# revB.net
KiCad netlist of a schematic drawn in EAGLE
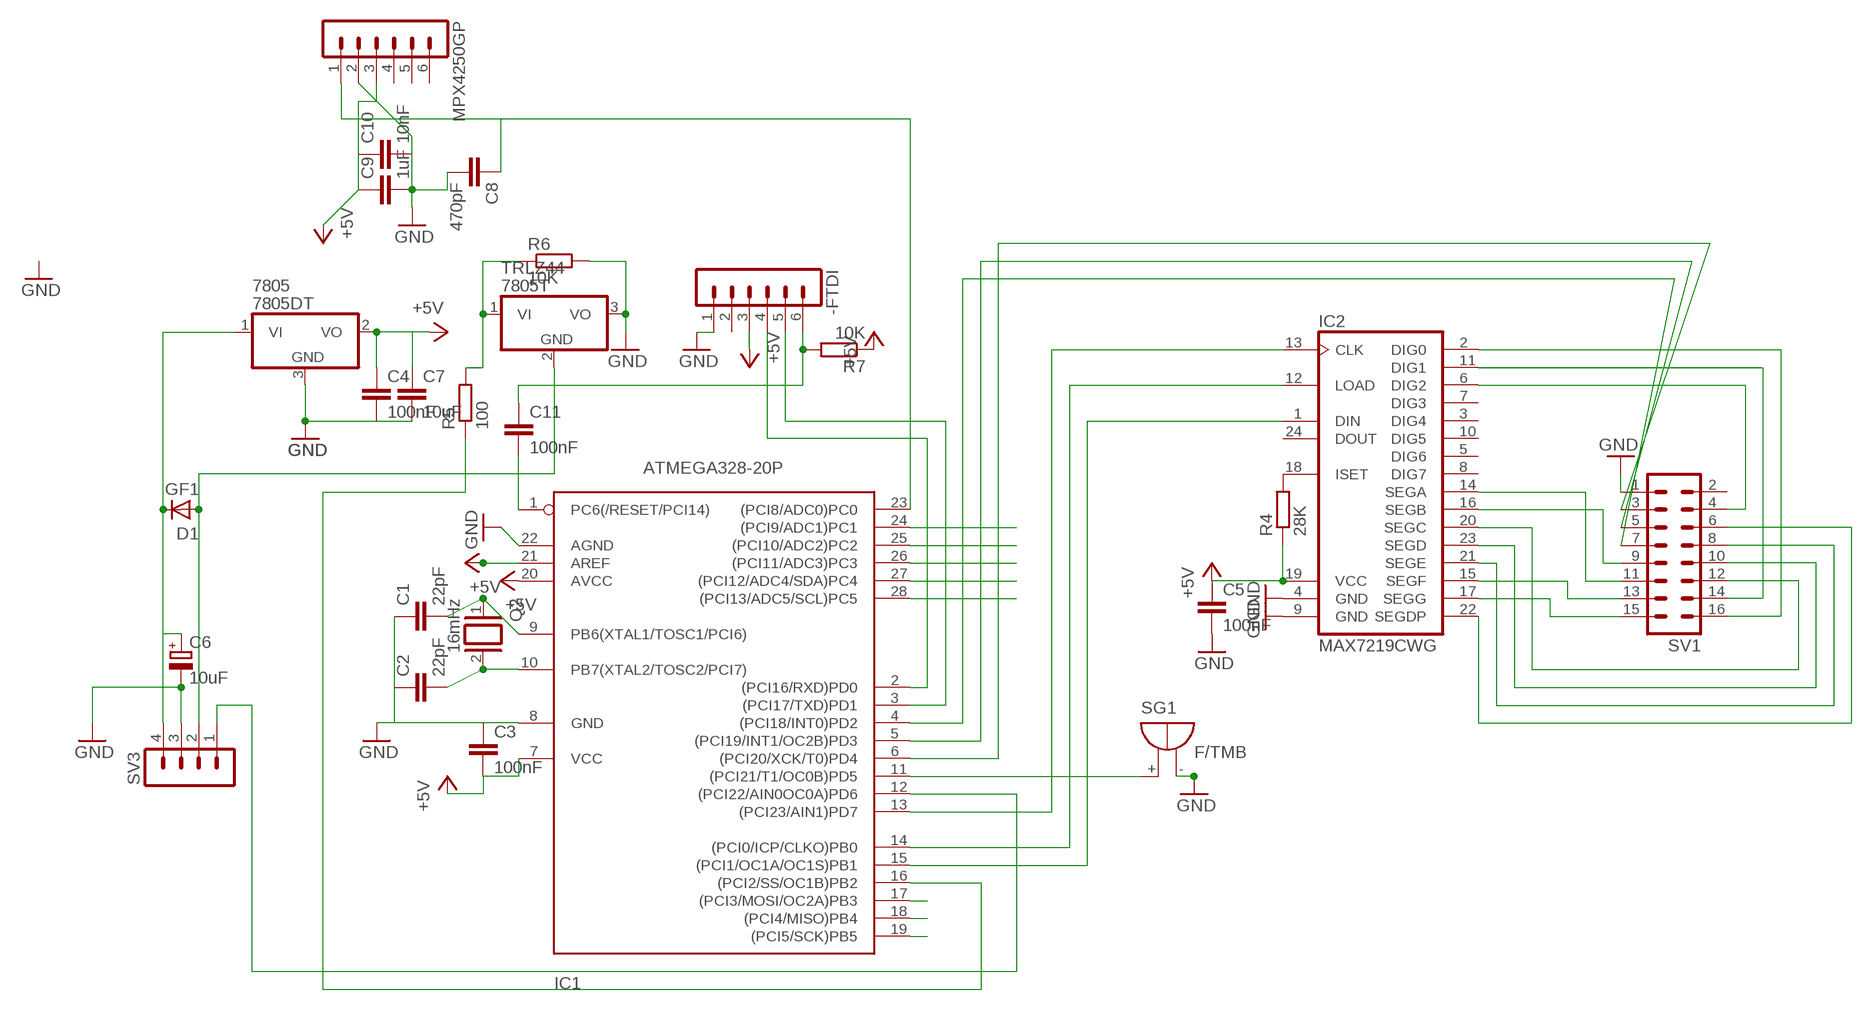
[diagram p0: schematic, sheet 1]

(export (version "E")
  (design (tool "Eeschema 10.0.6"))
  (components
    (comp (ref "-FTDI")
      (value "MA06-1")
      (footprint "eagle-import:MA06-1")
      (libsource (lib "eagle-import") (part "MA06-1"))
    )
    (comp (ref "7805")
      (value "7805DT")
      (footprint "eagle-import:TO252")
      (libsource (lib "eagle-import") (part "78DT05"))
    )
    (comp (ref "C1")
      (value "22pF")
      (footprint "eagle-import:C0805")
      (fields (field (name "MF") "MURATA") (field (name "MPN") "ERB21B5C2D220JDX1L"))
      (libsource (lib "eagle-import") (part "C-EUC0805"))
    )
    (comp (ref "C2")
      (value "22pF")
      (footprint "eagle-import:C0805")
      (fields (field (name "MF") "MURATA") (field (name "MPN") "ERB21B5C2D220JDX1L"))
      (libsource (lib "eagle-import") (part "C-EUC0805"))
    )
    (comp (ref "C3")
      (value "100nF")
      (footprint "eagle-import:C0805")
      (fields (field (name "MF") "KEMET") (field (name "MPN") "C0805X104K5RACTU"))
      (libsource (lib "eagle-import") (part "C-EUC0805"))
    )
    (comp (ref "C4")
      (value "100nF")
      (footprint "eagle-import:C0805")
      (fields (field (name "MF") "KEMET") (field (name "MPN") "C0805X104K5RACTU"))
      (libsource (lib "eagle-import") (part "C-EUC0805"))
    )
    (comp (ref "C5")
      (value "100nF")
      (footprint "eagle-import:C0805")
      (fields (field (name "MF") "KEMET") (field (name "MPN") "C0805X104K5RACTU"))
      (libsource (lib "eagle-import") (part "C-EUC0805"))
    )
    (comp (ref "C6")
      (value "10uF")
      (footprint "eagle-import:E2,5-6E")
      (libsource (lib "eagle-import") (part "CPOL-EUE2,5-6E"))
    )
    (comp (ref "C7")
      (value "10uF")
      (footprint "eagle-import:C0805")
      (fields (field (name "MF") "KEMET") (field (name "MPN") "C0805X104K5RACTU"))
      (libsource (lib "eagle-import") (part "C-EUC0805"))
    )
    (comp (ref "C8")
      (value "470pF")
      (footprint "eagle-import:C0805")
      (fields (field (name "MF") "KEMET") (field (name "MPN") "C0805X104K5RACTU"))
      (libsource (lib "eagle-import") (part "C-EUC0805"))
    )
    (comp (ref "C9")
      (value "1uF")
      (footprint "eagle-import:C0805")
      (fields (field (name "MF") "KEMET") (field (name "MPN") "C0805X104K5RACTU"))
      (libsource (lib "eagle-import") (part "C-EUC0805"))
    )
    (comp (ref "C10")
      (value "10nF")
      (footprint "eagle-import:C0805")
      (fields (field (name "MF") "KEMET") (field (name "MPN") "C0805X104K5RACTU"))
      (libsource (lib "eagle-import") (part "C-EUC0805"))
    )
    (comp (ref "C11")
      (value "100nF")
      (footprint "eagle-import:C0805")
      (fields (field (name "MF") "KEMET") (field (name "MPN") "C0805X104K5RACTU"))
      (libsource (lib "eagle-import") (part "C-EUC0805"))
    )
    (comp (ref "D1")
      (value "GF1")
      (footprint "eagle-import:SMA-DO214AC")
      (libsource (lib "eagle-import") (part "GF1"))
    )
    (comp (ref "IC1")
      (value "ATMEGA328-20P")
      (footprint "eagle-import:DIL28-3")
      (libsource (lib "eagle-import") (part "ATMEGA168P-20"))
    )
    (comp (ref "IC2")
      (value "MAX7219CWG")
      (footprint "eagle-import:MAX7219CWG")
      (libsource (lib "eagle-import") (part "MAX7219CWG"))
    )
    (comp (ref "MPX4250GP")
      (value "MA06-1")
      (footprint "eagle-import:MA06-1")
      (libsource (lib "eagle-import") (part "MA06-1"))
    )
    (comp (ref "Q2")
      (value "16mHz")
      (footprint "eagle-import:QS")
      (fields (field (name "MF") "EUROQUARTZ") (field (name "MPN") "16.000MHZ HC49/4H/30/50/40/18PF/ATF"))
      (libsource (lib "eagle-import") (part "XTAL/S"))
    )
    (comp (ref "R4")
      (value "28K")
      (footprint "eagle-import:R0805")
      (libsource (lib "eagle-import") (part "R-EU_R0805"))
    )
    (comp (ref "R5")
      (value "100")
      (footprint "eagle-import:R0805")
      (libsource (lib "eagle-import") (part "R-EU_R0805"))
    )
    (comp (ref "R6")
      (value "10K")
      (footprint "eagle-import:R0805")
      (libsource (lib "eagle-import") (part "R-EU_R0805"))
    )
    (comp (ref "R7")
      (value "10K")
      (footprint "eagle-import:R0805")
      (libsource (lib "eagle-import") (part "R-EU_R0805"))
    )
    (comp (ref "SG1")
      (value "F/TMB")
      (footprint "eagle-import:F_TMB")
      (libsource (lib "eagle-import") (part "F/TMB"))
    )
    (comp (ref "SV1")
      (value "MA08-2")
      (footprint "eagle-import:MA08-2")
      (libsource (lib "eagle-import") (part "MA08-2"))
    )
    (comp (ref "SV3")
      (value "MA04-1")
      (footprint "eagle-import:MA04-1")
      (libsource (lib "eagle-import") (part "MA04-1"))
    )
    (comp (ref "TRLZ44")
      (value "7805T")
      (footprint "eagle-import:TO220H")
      (libsource (lib "eagle-import") (part "78T05"))
    )
  )
  (nets
    (net (code "1") (name "+5V") (class "Default")
      (node (ref "-FTDI") (pin "3") (pinfunction "3_3") (pintype "passive"))
      (node (ref "7805") (pin "2") (pinfunction "VO_2") (pintype "passive"))
      (node (ref "C10") (pin "1") (pinfunction "1_1") (pintype "passive"))
      (node (ref "C3") (pin "2") (pinfunction "2_2") (pintype "passive"))
      (node (ref "C4") (pin "1") (pinfunction "1_1") (pintype "passive"))
      (node (ref "C5") (pin "1") (pinfunction "1_1") (pintype "passive"))
      (node (ref "C7") (pin "1") (pinfunction "1_1") (pintype "passive"))
      (node (ref "C9") (pin "1") (pinfunction "1_1") (pintype "passive"))
      (node (ref "IC1") (pin "20") (pinfunction "AVCC_20") (pintype "bidirectional"))
      (node (ref "IC1") (pin "21") (pinfunction "AREF_21") (pintype "bidirectional"))
      (node (ref "IC1") (pin "7") (pinfunction "VCC_7") (pintype "bidirectional"))
      (node (ref "IC2") (pin "19") (pinfunction "VCC_19") (pintype "power_in"))
      (node (ref "MPX4250GP") (pin "3") (pinfunction "3_3") (pintype "passive"))
      (node (ref "R4") (pin "1") (pinfunction "1_1") (pintype "passive"))
      (node (ref "R7") (pin "1") (pinfunction "1_1") (pintype "passive"))
    )
    (net (code "2") (name "GND") (class "Default")
      (node (ref "-FTDI") (pin "1") (pinfunction "1_1") (pintype "passive"))
      (node (ref "7805") (pin "3") (pinfunction "GND_3") (pintype "passive"))
      (node (ref "C1") (pin "1") (pinfunction "1_1") (pintype "passive"))
      (node (ref "C10") (pin "2") (pinfunction "2_2") (pintype "passive"))
      (node (ref "C2") (pin "1") (pinfunction "1_1") (pintype "passive"))
      (node (ref "C3") (pin "1") (pinfunction "1_1") (pintype "passive"))
      (node (ref "C4") (pin "2") (pinfunction "2_2") (pintype "passive"))
      (node (ref "C5") (pin "2") (pinfunction "2_2") (pintype "passive"))
      (node (ref "C6") (pin "-") (pinfunction "-_-") (pintype "passive"))
      (node (ref "C7") (pin "2") (pinfunction "2_2") (pintype "passive"))
      (node (ref "C8") (pin "2") (pinfunction "2_2") (pintype "passive"))
      (node (ref "C9") (pin "2") (pinfunction "2_2") (pintype "passive"))
      (node (ref "IC1") (pin "22") (pinfunction "AGND_22") (pintype "bidirectional"))
      (node (ref "IC1") (pin "8") (pinfunction "GND_8") (pintype "bidirectional"))
      (node (ref "IC2") (pin "4") (pinfunction "GND_4") (pintype "power_in"))
      (node (ref "IC2") (pin "9") (pinfunction "GND_9") (pintype "power_in"))
      (node (ref "MPX4250GP") (pin "2") (pinfunction "2_2") (pintype "passive"))
      (node (ref "R6") (pin "2") (pinfunction "2_2") (pintype "passive"))
      (node (ref "SG1") (pin "-") (pinfunction "-_-") (pintype "passive"))
      (node (ref "SV1") (pin "1") (pinfunction "1_1") (pintype "passive"))
      (node (ref "SV3") (pin "3") (pinfunction "3_3") (pintype "passive"))
      (node (ref "TRLZ44") (pin "3") (pinfunction "VO_3") (pintype "passive"))
    )
    (net (code "3") (name "Net-(-FTDI-Pad6)") (class "Default")
      (node (ref "-FTDI") (pin "6") (pinfunction "6_6") (pintype "passive"))
      (node (ref "C11") (pin "1") (pinfunction "1_1") (pintype "passive"))
      (node (ref "R7") (pin "2") (pinfunction "2_2") (pintype "passive"))
    )
    (net (code "4") (name "Net-(7805-VI)") (class "Default")
      (node (ref "7805") (pin "1") (pinfunction "VI_1") (pintype "input"))
      (node (ref "C6") (pin "+") (pinfunction "+_+") (pintype "passive"))
      (node (ref "D1") (pin "K") (pinfunction "C_K") (pintype "passive"))
      (node (ref "SV3") (pin "4") (pinfunction "4_4") (pintype "passive"))
    )
    (net (code "5") (name "Net-(IC1-(PCI0{slash}ICP{slash}CLKO)PB0)") (class "Default")
      (node (ref "IC1") (pin "14") (pinfunction "(PCI0/ICP/CLKO)PB0_14") (pintype "bidirectional"))
      (node (ref "IC2") (pin "12") (pinfunction "LOAD_12") (pintype "input"))
    )
    (net (code "6") (name "Net-(IC1-(PCI1{slash}OC1A{slash}OC1S)PB1)") (class "Default")
      (node (ref "IC1") (pin "15") (pinfunction "(PCI1/OC1A/OC1S)PB1_15") (pintype "bidirectional"))
      (node (ref "IC2") (pin "1") (pinfunction "DIN_1") (pintype "input"))
    )
    (net (code "7") (name "Net-(IC1-(PCI2{slash}SS{slash}OC1B)PB2)") (class "Default")
      (node (ref "IC1") (pin "16") (pinfunction "(PCI2/SS/OC1B)PB2_16") (pintype "bidirectional"))
      (node (ref "R5") (pin "1") (pinfunction "1_1") (pintype "passive"))
    )
    (net (code "8") (name "Net-(IC1-(PCI8{slash}ADC0)PC0)") (class "Default")
      (node (ref "C8") (pin "1") (pinfunction "1_1") (pintype "passive"))
      (node (ref "IC1") (pin "23") (pinfunction "(PCI8/ADC0)PC0_23") (pintype "bidirectional"))
      (node (ref "MPX4250GP") (pin "1") (pinfunction "1_1") (pintype "passive"))
    )
    (net (code "9") (name "Net-(IC1-(PCI16{slash}RXD)PD0)") (class "Default")
      (node (ref "-FTDI") (pin "4") (pinfunction "4_4") (pintype "passive"))
      (node (ref "IC1") (pin "2") (pinfunction "(PCI16/RXD)PD0_2") (pintype "bidirectional"))
    )
    (net (code "10") (name "Net-(IC1-(PCI17{slash}TXD)PD1)") (class "Default")
      (node (ref "-FTDI") (pin "5") (pinfunction "5_5") (pintype "passive"))
      (node (ref "IC1") (pin "3") (pinfunction "(PCI17/TXD)PD1_3") (pintype "bidirectional"))
    )
    (net (code "11") (name "Net-(IC1-(PCI18{slash}INT0)PD2)") (class "Default")
      (node (ref "IC1") (pin "4") (pinfunction "(PCI18/INT0)PD2_4") (pintype "bidirectional"))
      (node (ref "SV1") (pin "7") (pinfunction "7_7") (pintype "passive"))
    )
    (net (code "12") (name "Net-(IC1-(PCI19{slash}INT1{slash}OC2B)PD3)") (class "Default")
      (node (ref "IC1") (pin "5") (pinfunction "(PCI19/INT1/OC2B)PD3_5") (pintype "bidirectional"))
      (node (ref "SV1") (pin "5") (pinfunction "5_5") (pintype "passive"))
    )
    (net (code "13") (name "Net-(IC1-(PCI20{slash}XCK{slash}T0)PD4)") (class "Default")
      (node (ref "IC1") (pin "6") (pinfunction "(PCI20/XCK/T0)PD4_6") (pintype "bidirectional"))
      (node (ref "SV1") (pin "3") (pinfunction "3_3") (pintype "passive"))
    )
    (net (code "14") (name "Net-(IC1-(PCI21{slash}T1{slash}OC0B)PD5)") (class "Default")
      (node (ref "IC1") (pin "11") (pinfunction "(PCI21/T1/OC0B)PD5_11") (pintype "bidirectional"))
      (node (ref "SG1") (pin "+") (pinfunction "+_+") (pintype "passive"))
    )
    (net (code "15") (name "Net-(IC1-(PCI22{slash}AIN0OC0A)PD6)") (class "Default")
      (node (ref "IC1") (pin "12") (pinfunction "(PCI22/AIN0OC0A)PD6_12") (pintype "bidirectional"))
      (node (ref "SV3") (pin "1") (pinfunction "1_1") (pintype "passive"))
    )
    (net (code "16") (name "Net-(IC1-(PCI23{slash}AIN1)PD7)") (class "Default")
      (node (ref "IC1") (pin "13") (pinfunction "(PCI23/AIN1)PD7_13") (pintype "bidirectional"))
      (node (ref "IC2") (pin "13") (pinfunction "CLK_13") (pintype "input"))
    )
    (net (code "17") (name "Net-(IC1-PB6(XTAL1{slash}TOSC1{slash}PCI6))") (class "Default")
      (node (ref "C1") (pin "2") (pinfunction "2_2") (pintype "passive"))
      (node (ref "IC1") (pin "9") (pinfunction "PB6(XTAL1/TOSC1/PCI6)_9") (pintype "bidirectional"))
      (node (ref "Q2") (pin "1") (pinfunction "1_1") (pintype "passive"))
    )
    (net (code "18") (name "Net-(IC1-PB7(XTAL2{slash}TOSC2{slash}PCI7))") (class "Default")
      (node (ref "C2") (pin "2") (pinfunction "2_2") (pintype "passive"))
      (node (ref "IC1") (pin "10") (pinfunction "PB7(XTAL2/TOSC2/PCI7)_10") (pintype "bidirectional"))
      (node (ref "Q2") (pin "2") (pinfunction "2_2") (pintype "passive"))
    )
    (net (code "19") (name "Net-(IC1-PC6({slash}RESET{slash}PCI14))") (class "Default")
      (node (ref "C11") (pin "2") (pinfunction "2_2") (pintype "passive"))
      (node (ref "IC1") (pin "1") (pinfunction "PC6(/RESET/PCI14)_1") (pintype "bidirectional"))
    )
    (net (code "20") (name "Net-(IC2-DIG0)") (class "Default")
      (node (ref "IC2") (pin "2") (pinfunction "DIG0_2") (pintype "output"))
      (node (ref "SV1") (pin "16") (pinfunction "16_16") (pintype "passive"))
    )
    (net (code "21") (name "Net-(IC2-DIG1)") (class "Default")
      (node (ref "IC2") (pin "11") (pinfunction "DIG1_11") (pintype "output"))
      (node (ref "SV1") (pin "14") (pinfunction "14_14") (pintype "passive"))
    )
    (net (code "22") (name "Net-(IC2-DIG2)") (class "Default")
      (node (ref "IC2") (pin "6") (pinfunction "DIG2_6") (pintype "output"))
      (node (ref "SV1") (pin "4") (pinfunction "4_4") (pintype "passive"))
    )
    (net (code "23") (name "Net-(IC2-ISET)") (class "Default")
      (node (ref "IC2") (pin "18") (pinfunction "ISET_18") (pintype "input"))
      (node (ref "R4") (pin "2") (pinfunction "2_2") (pintype "passive"))
    )
    (net (code "24") (name "Net-(IC2-SEGA)") (class "Default")
      (node (ref "IC2") (pin "14") (pinfunction "SEGA_14") (pintype "output"))
      (node (ref "SV1") (pin "11") (pinfunction "11_11") (pintype "passive"))
    )
    (net (code "25") (name "Net-(IC2-SEGB)") (class "Default")
      (node (ref "IC2") (pin "16") (pinfunction "SEGB_16") (pintype "output"))
      (node (ref "SV1") (pin "9") (pinfunction "9_9") (pintype "passive"))
    )
    (net (code "26") (name "Net-(IC2-SEGC)") (class "Default")
      (node (ref "IC2") (pin "20") (pinfunction "SEGC_20") (pintype "output"))
      (node (ref "SV1") (pin "12") (pinfunction "12_12") (pintype "passive"))
    )
    (net (code "27") (name "Net-(IC2-SEGD)") (class "Default")
      (node (ref "IC2") (pin "23") (pinfunction "SEGD_23") (pintype "output"))
      (node (ref "SV1") (pin "10") (pinfunction "10_10") (pintype "passive"))
    )
    (net (code "28") (name "Net-(IC2-SEGDP)") (class "Default")
      (node (ref "IC2") (pin "22") (pinfunction "SEGDP_22") (pintype "output"))
      (node (ref "SV1") (pin "6") (pinfunction "6_6") (pintype "passive"))
    )
    (net (code "29") (name "Net-(IC2-SEGE)") (class "Default")
      (node (ref "IC2") (pin "21") (pinfunction "SEGE_21") (pintype "output"))
      (node (ref "SV1") (pin "8") (pinfunction "8_8") (pintype "passive"))
    )
    (net (code "30") (name "Net-(IC2-SEGF)") (class "Default")
      (node (ref "IC2") (pin "15") (pinfunction "SEGF_15") (pintype "output"))
      (node (ref "SV1") (pin "13") (pinfunction "13_13") (pintype "passive"))
    )
    (net (code "31") (name "Net-(IC2-SEGG)") (class "Default")
      (node (ref "IC2") (pin "17") (pinfunction "SEGG_17") (pintype "output"))
      (node (ref "SV1") (pin "15") (pinfunction "15_15") (pintype "passive"))
    )
    (net (code "32") (name "Net-(TRLZ44-GND)") (class "Default")
      (node (ref "D1") (pin "A") (pinfunction "A_A") (pintype "passive"))
      (node (ref "SV3") (pin "2") (pinfunction "2_2") (pintype "passive"))
      (node (ref "TRLZ44") (pin "2") (pinfunction "GND_2") (pintype "passive"))
    )
    (net (code "33") (name "Net-(TRLZ44-VI)") (class "Default")
      (node (ref "R5") (pin "2") (pinfunction "2_2") (pintype "passive"))
      (node (ref "R6") (pin "1") (pinfunction "1_1") (pintype "passive"))
      (node (ref "TRLZ44") (pin "1") (pinfunction "VI_1") (pintype "input"))
    )
    (net (code "34") (name "unconnected-(-FTDI-Pad2)") (class "Default")
      (node (ref "-FTDI") (pin "2") (pinfunction "2_2") (pintype "passive"))
    )
    (net (code "35") (name "unconnected-(IC1-(PCI3{slash}MOSI{slash}OC2A)PB3-Pad17)") (class "Default")
      (node (ref "IC1") (pin "17") (pinfunction "(PCI3/MOSI/OC2A)PB3_17") (pintype "bidirectional"))
    )
    (net (code "36") (name "unconnected-(IC1-(PCI4{slash}MISO)PB4-Pad18)") (class "Default")
      (node (ref "IC1") (pin "18") (pinfunction "(PCI4/MISO)PB4_18") (pintype "bidirectional"))
    )
    (net (code "37") (name "unconnected-(IC1-(PCI5{slash}SCK)PB5-Pad19)") (class "Default")
      (node (ref "IC1") (pin "19") (pinfunction "(PCI5/SCK)PB5_19") (pintype "bidirectional"))
    )
    (net (code "38") (name "unconnected-(IC1-(PCI9{slash}ADC1)PC1-Pad24)") (class "Default")
      (node (ref "IC1") (pin "24") (pinfunction "(PCI9/ADC1)PC1_24") (pintype "bidirectional"))
    )
    (net (code "39") (name "unconnected-(IC1-(PCI10{slash}ADC2)PC2-Pad25)") (class "Default")
      (node (ref "IC1") (pin "25") (pinfunction "(PCI10/ADC2)PC2_25") (pintype "bidirectional"))
    )
    (net (code "40") (name "unconnected-(IC1-(PCI11{slash}ADC3)PC3-Pad26)") (class "Default")
      (node (ref "IC1") (pin "26") (pinfunction "(PCI11/ADC3)PC3_26") (pintype "bidirectional"))
    )
    (net (code "41") (name "unconnected-(IC1-(PCI12{slash}ADC4{slash}SDA)PC4-Pad27)") (class "Default")
      (node (ref "IC1") (pin "27") (pinfunction "(PCI12/ADC4/SDA)PC4_27") (pintype "bidirectional"))
    )
    (net (code "42") (name "unconnected-(IC1-(PCI13{slash}ADC5{slash}SCL)PC5-Pad28)") (class "Default")
      (node (ref "IC1") (pin "28") (pinfunction "(PCI13/ADC5/SCL)PC5_28") (pintype "bidirectional"))
    )
    (net (code "43") (name "unconnected-(IC2-DIG3-Pad7)") (class "Default")
      (node (ref "IC2") (pin "7") (pinfunction "DIG3_7") (pintype "output"))
    )
    (net (code "44") (name "unconnected-(IC2-DIG4-Pad3)") (class "Default")
      (node (ref "IC2") (pin "3") (pinfunction "DIG4_3") (pintype "output"))
    )
    (net (code "45") (name "unconnected-(IC2-DIG5-Pad10)") (class "Default")
      (node (ref "IC2") (pin "10") (pinfunction "DIG5_10") (pintype "output"))
    )
    (net (code "46") (name "unconnected-(IC2-DIG6-Pad5)") (class "Default")
      (node (ref "IC2") (pin "5") (pinfunction "DIG6_5") (pintype "output"))
    )
    (net (code "47") (name "unconnected-(IC2-DIG7-Pad8)") (class "Default")
      (node (ref "IC2") (pin "8") (pinfunction "DIG7_8") (pintype "output"))
    )
    (net (code "48") (name "unconnected-(IC2-DOUT-Pad24)") (class "Default")
      (node (ref "IC2") (pin "24") (pinfunction "DOUT_24") (pintype "output"))
    )
    (net (code "49") (name "unconnected-(MPX4250GP-Pad4)") (class "Default")
      (node (ref "MPX4250GP") (pin "4") (pinfunction "4_4") (pintype "passive"))
    )
    (net (code "50") (name "unconnected-(MPX4250GP-Pad5)") (class "Default")
      (node (ref "MPX4250GP") (pin "5") (pinfunction "5_5") (pintype "passive"))
    )
    (net (code "51") (name "unconnected-(MPX4250GP-Pad6)") (class "Default")
      (node (ref "MPX4250GP") (pin "6") (pinfunction "6_6") (pintype "passive"))
    )
    (net (code "52") (name "unconnected-(SV1-Pad2)") (class "Default")
      (node (ref "SV1") (pin "2") (pinfunction "2_2") (pintype "passive"))
    )
  )
)
